# SCH_tic-tac2_2024-06-27_1.net
KiCad netlist of a schematic drawn in EasyEDA
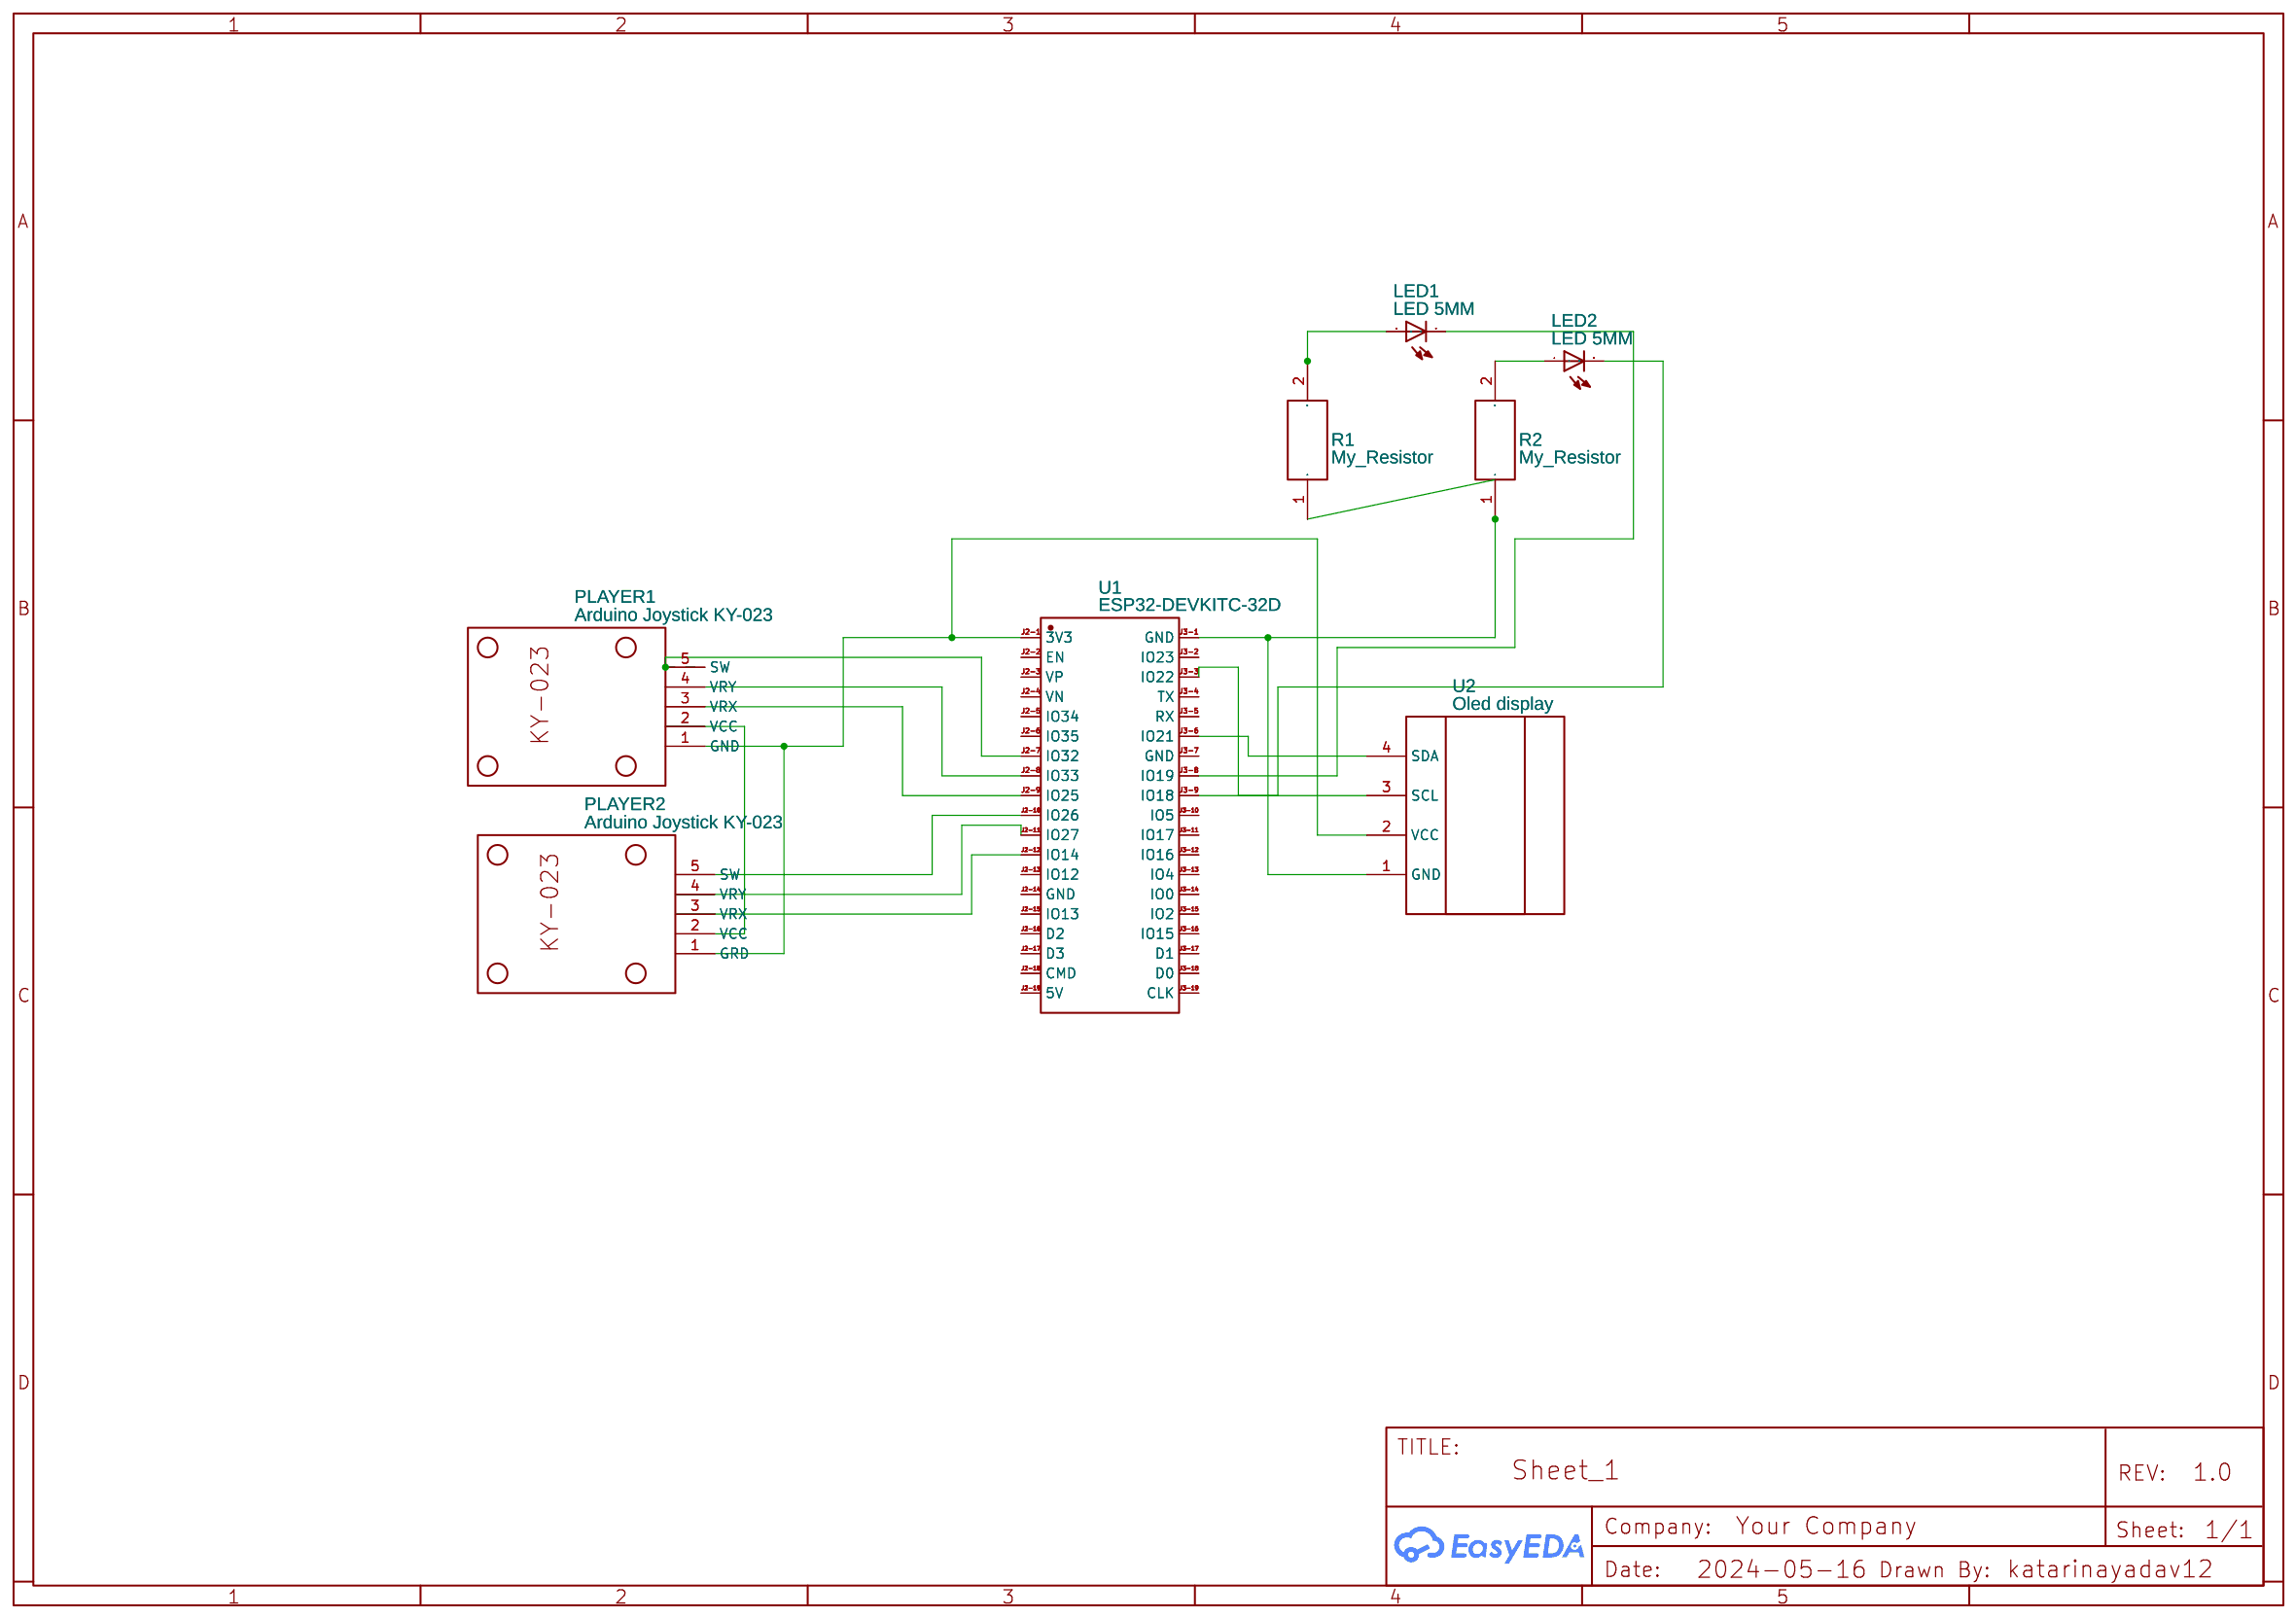
[diagram p0: schematic sheet]

(export (version "E")
  (design (tool "Eeschema 10.0.6"))
  (components
    (comp (ref "LED1") (value "LED 5MM") (libsource (lib "") (part "LED 5MM")))
    (comp (ref "LED2") (value "LED 5MM") (libsource (lib "") (part "LED 5MM")))
    (comp (ref "PLAYER1")
      (value "Arduino Joystick KY-023")
      (libsource (lib "") (part "Arduino Joystick KY-023"))
    )
    (comp (ref "PLAYER2")
      (value "Arduino Joystick KY-023")
      (libsource (lib "") (part "Arduino Joystick KY-023_1"))
    )
    (comp (ref "R1") (value "My_Resistor") (libsource (lib "") (part "My_Resistor")))
    (comp (ref "R2") (value "My_Resistor") (libsource (lib "") (part "My_Resistor")))
    (comp (ref "U1")
      (value "ESP32-DEVKITC-32D")
      (fields
        (field (name "Manufacturer Part") "ESP32-DevKitC-32D")
        (field (name "Manufacturer") "ESPRESSIF(乐鑫)")
      )
      (libsource (lib "") (part "ESP32-DEVKITC-32D"))
    )
    (comp (ref "U2") (value "Oled display") (libsource (lib "") (part "Oled display")))
  )
  (nets
    (net (code "1") (name "Net-(LED1-A)") (class "Default")
      (node (ref "LED1") (pin "1") (pinfunction "A_1") (pintype "unspecified"))
      (node (ref "R1") (pin "2") (pinfunction "2_2") (pintype "unspecified"))
    )
    (net (code "2") (name "Net-(LED1-C)") (class "Default")
      (node (ref "LED1") (pin "2") (pinfunction "C_2") (pintype "unspecified"))
      (node (ref "U1") (pin "J3-8") (pinfunction "IO19_J3-8") (pintype "unspecified"))
    )
    (net (code "3") (name "Net-(LED2-A)") (class "Default")
      (node (ref "LED2") (pin "1") (pinfunction "A_1") (pintype "unspecified"))
      (node (ref "R2") (pin "2") (pinfunction "2_2") (pintype "unspecified"))
    )
    (net (code "4") (name "Net-(LED2-C)") (class "Default")
      (node (ref "LED2") (pin "2") (pinfunction "C_2") (pintype "unspecified"))
      (node (ref "U1") (pin "J3-9") (pinfunction "IO18_J3-9") (pintype "unspecified"))
    )
    (net (code "5") (name "Net-(PLAYER1-SW)") (class "Default")
      (node (ref "PLAYER1") (pin "5") (pinfunction "SW_5") (pintype "unspecified"))
      (node (ref "U1") (pin "J2-7") (pinfunction "IO32_J2-7") (pintype "unspecified"))
    )
    (net (code "6") (name "Net-(PLAYER1-VRY)") (class "Default")
      (node (ref "PLAYER1") (pin "4") (pinfunction "VRY_4") (pintype "unspecified"))
      (node (ref "U1") (pin "J2-8") (pinfunction "IO33_J2-8") (pintype "unspecified"))
    )
    (net (code "7") (name "Net-(PLAYER2-SW)") (class "Default")
      (node (ref "PLAYER2") (pin "5") (pinfunction "SW_5") (pintype "unspecified"))
      (node (ref "U1") (pin "J2-10") (pinfunction "IO26_J2-10") (pintype "unspecified"))
    )
    (net (code "8") (name "Net-(PLAYER2-VRX)") (class "Default")
      (node (ref "PLAYER2") (pin "3") (pinfunction "VRX_3") (pintype "unspecified"))
      (node (ref "U1") (pin "J2-12") (pinfunction "IO14_J2-12") (pintype "unspecified"))
    )
    (net (code "9") (name "Net-(PLAYER2-VRY)") (class "Default")
      (node (ref "PLAYER2") (pin "4") (pinfunction "VRY_4") (pintype "unspecified"))
      (node (ref "U1") (pin "J2-11") (pinfunction "IO27_J2-11") (pintype "unspecified"))
    )
    (net (code "10") (name "Net-(U1-3V3)") (class "Default")
      (node (ref "U1") (pin "J2-1") (pinfunction "3V3_J2-1") (pintype "unspecified"))
      (node (ref "U2") (pin "2") (pinfunction "VCC_2") (pintype "unspecified"))
    )
    (net (code "11") (name "Net-(U1-IO21)") (class "Default")
      (node (ref "U1") (pin "J3-6") (pinfunction "IO21_J3-6") (pintype "unspecified"))
      (node (ref "U2") (pin "4") (pinfunction "SDA_4") (pintype "unspecified"))
    )
    (net (code "12") (name "Net-(U1-IO22)") (class "Default")
      (node (ref "U1") (pin "J3-3") (pinfunction "IO22_J3-3") (pintype "unspecified"))
      (node (ref "U2") (pin "3") (pinfunction "SCL_3") (pintype "unspecified"))
    )
    (net (code "13") (name "Net-(U2-GND)") (class "Default")
      (node (ref "R1") (pin "1") (pinfunction "1_1") (pintype "unspecified"))
      (node (ref "R2") (pin "1") (pinfunction "1_1") (pintype "unspecified"))
      (node (ref "U1") (pin "J3-1") (pinfunction "GND_J3-1") (pintype "unspecified"))
      (node (ref "U2") (pin "1") (pinfunction "GND_1") (pintype "unspecified"))
    )
    (net (code "14") (name "unconnected-(PLAYER1-GND-Pad1)") (class "Default")
      (node (ref "PLAYER1") (pin "1") (pinfunction "GND_1") (pintype "unspecified"))
    )
    (net (code "15") (name "unconnected-(PLAYER1-VCC-Pad2)") (class "Default")
      (node (ref "PLAYER1") (pin "2") (pinfunction "VCC_2") (pintype "unspecified"))
    )
    (net (code "16") (name "unconnected-(PLAYER1-VRX-Pad3)") (class "Default")
      (node (ref "PLAYER1") (pin "3") (pinfunction "VRX_3") (pintype "unspecified"))
    )
    (net (code "17") (name "unconnected-(PLAYER2-GRD-Pad1)") (class "Default")
      (node (ref "PLAYER2") (pin "1") (pinfunction "GRD_1") (pintype "unspecified"))
    )
    (net (code "18") (name "unconnected-(PLAYER2-VCC-Pad2)") (class "Default")
      (node (ref "PLAYER2") (pin "2") (pinfunction "VCC_2") (pintype "unspecified"))
    )
    (net (code "19") (name "unconnected-(U1-5V-PadJ2-19)") (class "Default")
      (node (ref "U1") (pin "J2-19") (pinfunction "5V_J2-19") (pintype "unspecified"))
    )
    (net (code "20") (name "unconnected-(U1-CLK-PadJ3-19)") (class "Default")
      (node (ref "U1") (pin "J3-19") (pinfunction "CLK_J3-19") (pintype "unspecified"))
    )
    (net (code "21") (name "unconnected-(U1-CMD-PadJ2-18)") (class "Default")
      (node (ref "U1") (pin "J2-18") (pinfunction "CMD_J2-18") (pintype "unspecified"))
    )
    (net (code "22") (name "unconnected-(U1-D0-PadJ3-18)") (class "Default")
      (node (ref "U1") (pin "J3-18") (pinfunction "D0_J3-18") (pintype "unspecified"))
    )
    (net (code "23") (name "unconnected-(U1-D1-PadJ3-17)") (class "Default")
      (node (ref "U1") (pin "J3-17") (pinfunction "D1_J3-17") (pintype "unspecified"))
    )
    (net (code "24") (name "unconnected-(U1-D2-PadJ2-16)") (class "Default")
      (node (ref "U1") (pin "J2-16") (pinfunction "D2_J2-16") (pintype "unspecified"))
    )
    (net (code "25") (name "unconnected-(U1-D3-PadJ2-17)") (class "Default")
      (node (ref "U1") (pin "J2-17") (pinfunction "D3_J2-17") (pintype "unspecified"))
    )
    (net (code "26") (name "unconnected-(U1-EN-PadJ2-2)") (class "Default")
      (node (ref "U1") (pin "J2-2") (pinfunction "EN_J2-2") (pintype "unspecified"))
    )
    (net (code "27") (name "unconnected-(U1-GND-PadJ2-14)") (class "Default")
      (node (ref "U1") (pin "J2-14") (pinfunction "GND_J2-14") (pintype "unspecified"))
    )
    (net (code "28") (name "unconnected-(U1-GND-PadJ3-7)") (class "Default")
      (node (ref "U1") (pin "J3-7") (pinfunction "GND_J3-7") (pintype "unspecified"))
    )
    (net (code "29") (name "unconnected-(U1-IO0-PadJ3-14)") (class "Default")
      (node (ref "U1") (pin "J3-14") (pinfunction "IO0_J3-14") (pintype "unspecified"))
    )
    (net (code "30") (name "unconnected-(U1-IO2-PadJ3-15)") (class "Default")
      (node (ref "U1") (pin "J3-15") (pinfunction "IO2_J3-15") (pintype "unspecified"))
    )
    (net (code "31") (name "unconnected-(U1-IO4-PadJ3-13)") (class "Default")
      (node (ref "U1") (pin "J3-13") (pinfunction "IO4_J3-13") (pintype "unspecified"))
    )
    (net (code "32") (name "unconnected-(U1-IO5-PadJ3-10)") (class "Default")
      (node (ref "U1") (pin "J3-10") (pinfunction "IO5_J3-10") (pintype "unspecified"))
    )
    (net (code "33") (name "unconnected-(U1-IO12-PadJ2-13)") (class "Default")
      (node (ref "U1") (pin "J2-13") (pinfunction "IO12_J2-13") (pintype "unspecified"))
    )
    (net (code "34") (name "unconnected-(U1-IO13-PadJ2-15)") (class "Default")
      (node (ref "U1") (pin "J2-15") (pinfunction "IO13_J2-15") (pintype "unspecified"))
    )
    (net (code "35") (name "unconnected-(U1-IO15-PadJ3-16)") (class "Default")
      (node (ref "U1") (pin "J3-16") (pinfunction "IO15_J3-16") (pintype "unspecified"))
    )
    (net (code "36") (name "unconnected-(U1-IO16-PadJ3-12)") (class "Default")
      (node (ref "U1") (pin "J3-12") (pinfunction "IO16_J3-12") (pintype "unspecified"))
    )
    (net (code "37") (name "unconnected-(U1-IO17-PadJ3-11)") (class "Default")
      (node (ref "U1") (pin "J3-11") (pinfunction "IO17_J3-11") (pintype "unspecified"))
    )
    (net (code "38") (name "unconnected-(U1-IO23-PadJ3-2)") (class "Default")
      (node (ref "U1") (pin "J3-2") (pinfunction "IO23_J3-2") (pintype "unspecified"))
    )
    (net (code "39") (name "unconnected-(U1-IO25-PadJ2-9)") (class "Default")
      (node (ref "U1") (pin "J2-9") (pinfunction "IO25_J2-9") (pintype "unspecified"))
    )
    (net (code "40") (name "unconnected-(U1-IO34-PadJ2-5)") (class "Default")
      (node (ref "U1") (pin "J2-5") (pinfunction "IO34_J2-5") (pintype "unspecified"))
    )
    (net (code "41") (name "unconnected-(U1-IO35-PadJ2-6)") (class "Default")
      (node (ref "U1") (pin "J2-6") (pinfunction "IO35_J2-6") (pintype "unspecified"))
    )
    (net (code "42") (name "unconnected-(U1-RX-PadJ3-5)") (class "Default")
      (node (ref "U1") (pin "J3-5") (pinfunction "RX_J3-5") (pintype "unspecified"))
    )
    (net (code "43") (name "unconnected-(U1-TX-PadJ3-4)") (class "Default")
      (node (ref "U1") (pin "J3-4") (pinfunction "TX_J3-4") (pintype "unspecified"))
    )
    (net (code "44") (name "unconnected-(U1-VN-PadJ2-4)") (class "Default")
      (node (ref "U1") (pin "J2-4") (pinfunction "VN_J2-4") (pintype "unspecified"))
    )
    (net (code "45") (name "unconnected-(U1-VP-PadJ2-3)") (class "Default")
      (node (ref "U1") (pin "J2-3") (pinfunction "VP_J2-3") (pintype "unspecified"))
    )
  )
)
